# Sheet_4.net
KiCad netlist of a schematic drawn in Altium Designer
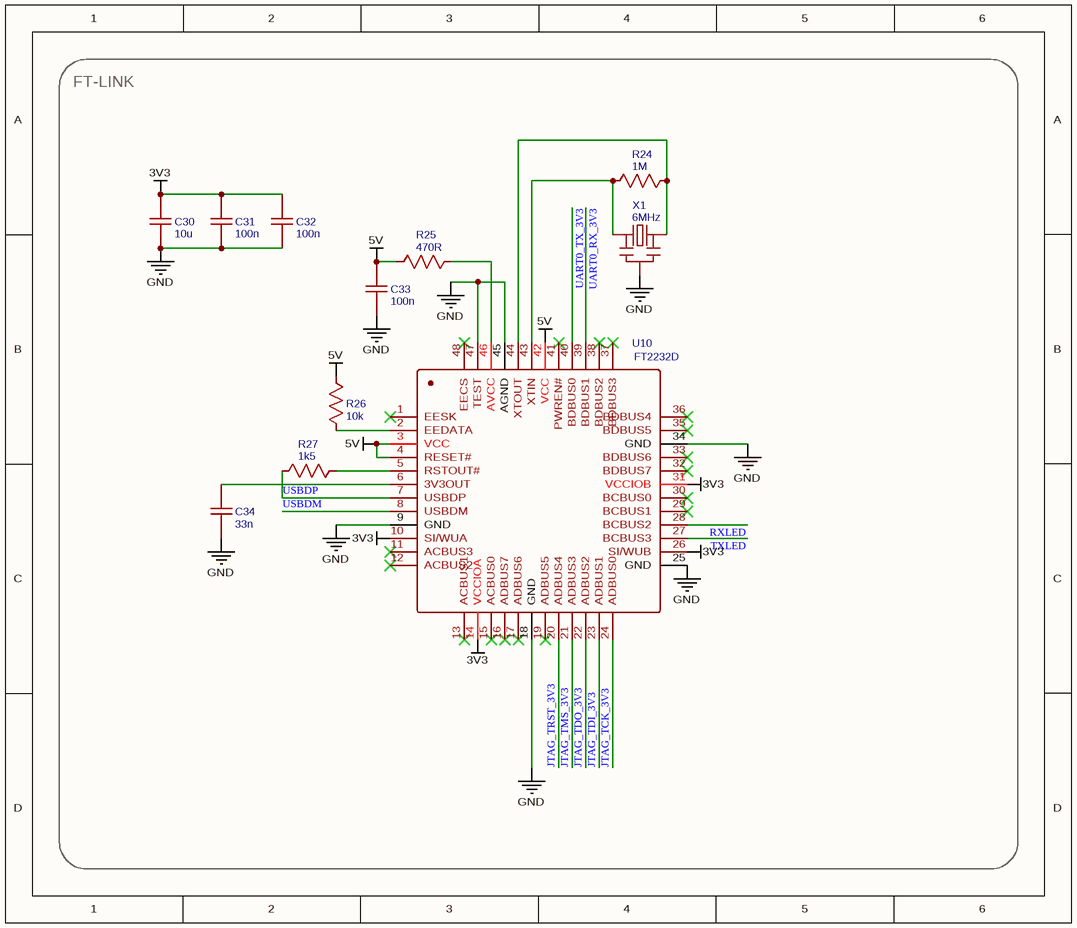
[diagram p0: Sheet_4.schdoc]

(export (version "E")
  (design (tool "Eeschema 10.0.6"))
  (components
    (comp (ref "C30")
      (value "10u")
      (footprint "CAPA-0603")
      (fields
        (field (name "BOM_SUPPLIER PART") "C19702")
        (field (name "BOM_MANUFACTURER PART") "CL10A106KP8NNNC")
      )
      (libsource (lib "altium-import") (part "root_1_10u_"))
    )
    (comp (ref "C31")
      (value "100n")
      (footprint "CAPA-0402")
      (fields
        (field (name "BOM_SUPPLIER PART") "C307331")
        (field (name "BOM_MANUFACTURER PART") "CL05B104KB54PNC")
      )
      (libsource (lib "altium-import") (part "root_1_100n_"))
    )
    (comp (ref "C32")
      (value "100n")
      (footprint "CAPA-0402")
      (fields
        (field (name "BOM_SUPPLIER PART") "C307331")
        (field (name "BOM_MANUFACTURER PART") "CL05B104KB54PNC")
      )
      (libsource (lib "altium-import") (part "root_1_100n_"))
    )
    (comp (ref "C33")
      (value "100n")
      (footprint "CAPA-0402")
      (fields
        (field (name "BOM_SUPPLIER PART") "C307331")
        (field (name "BOM_MANUFACTURER PART") "CL05B104KB54PNC")
      )
      (libsource (lib "altium-import") (part "root_1_100n_"))
    )
    (comp (ref "C34")
      (value "33n")
      (footprint "CAPA-0603")
      (fields
        (field (name "BOM_SUPPLIER PART") "C21117")
        (field (name "BOM_MANUFACTURER PART") "CL10B333KB8NNNC")
      )
      (libsource (lib "altium-import") (part "root_1_33n_"))
    )
    (comp (ref "R24")
      (value "1M")
      (footprint "RES-0402")
      (fields
        (field (name "BOM_SUPPLIER PART") "C26083")
        (field (name "BOM_MANUFACTURER PART") "0402WGF1004TCE")
      )
      (libsource (lib "altium-import") (part "root_0_1M_"))
    )
    (comp (ref "R25")
      (value "470R")
      (footprint "RES-0402")
      (fields
        (field (name "BOM_SUPPLIER PART") "C25117")
        (field (name "BOM_MANUFACTURER PART") "0402WGF4700TCE")
      )
      (libsource (lib "altium-import") (part "root_0_470R_"))
    )
    (comp (ref "R26")
      (value "10k")
      (footprint "RES-0402")
      (fields
        (field (name "BOM_SUPPLIER PART") "C25744")
        (field (name "BOM_MANUFACTURER PART") "0402WGF1002TCE")
      )
      (libsource (lib "altium-import") (part "root_3_10k_"))
    )
    (comp (ref "R27")
      (value "1k5")
      (footprint "RES-0402")
      (fields
        (field (name "BOM_SUPPLIER PART") "C25867")
        (field (name "BOM_MANUFACTURER PART") "0402WGF1501TCE")
      )
      (libsource (lib "altium-import") (part "root_0_1k5_"))
    )
    (comp (ref "U10")
      (value "FT2232D")
      (footprint "LQFP-48_L7.0-W7.0-P0.50-LS9.0-BL")
      (fields (field (name "BOM_SUPPLIER PART") "C428116"))
      (libsource (lib "altium-import") (part "root_0_FT2232D_"))
    )
    (comp (ref "X1")
      (value "6MHz")
      (footprint "CRYSTAL-SMD_3P-L4.5-W2.0-L")
      (fields
        (field (name "BOM_MANUFACTURER PART") "CSTCR6M00G53-R0")
        (field (name "BOM_SUPPLIER PART") "C85845")
      )
      (libsource (lib "altium-import") (part "root_0_6MHz_"))
    )
  )
  (nets
    (net (code "1") (name "/JTAG_TCK_3V3") (class "Default")
      (node (ref "U10") (pin "24") (pinfunction "ADBUS0_24") (pintype "passive"))
    )
    (net (code "2") (name "/JTAG_TDI_3V3") (class "Default")
      (node (ref "U10") (pin "23") (pinfunction "ADBUS1_23") (pintype "passive"))
    )
    (net (code "3") (name "/JTAG_TDO_3V3") (class "Default")
      (node (ref "U10") (pin "22") (pinfunction "ADBUS2_22") (pintype "passive"))
    )
    (net (code "4") (name "/JTAG_TMS_3V3") (class "Default")
      (node (ref "U10") (pin "21") (pinfunction "ADBUS3_21") (pintype "passive"))
    )
    (net (code "5") (name "/JTAG_TRST_3V3") (class "Default")
      (node (ref "U10") (pin "20") (pinfunction "ADBUS4_20") (pintype "passive"))
    )
    (net (code "6") (name "/RXLED") (class "Default")
      (node (ref "U10") (pin "28") (pinfunction "BCBUS2_28") (pintype "passive"))
    )
    (net (code "7") (name "/TXLED") (class "Default")
      (node (ref "U10") (pin "27") (pinfunction "BCBUS3_27") (pintype "passive"))
    )
    (net (code "8") (name "/UART0_RX_3V3") (class "Default")
      (node (ref "U10") (pin "39") (pinfunction "BDBUS1_39") (pintype "passive"))
    )
    (net (code "9") (name "/UART0_TX_3V3") (class "Default")
      (node (ref "U10") (pin "40") (pinfunction "BDBUS0_40") (pintype "passive"))
    )
    (net (code "10") (name "/USBDM") (class "Default")
      (node (ref "U10") (pin "8") (pinfunction "USBDM_8") (pintype "passive"))
    )
    (net (code "11") (name "/USBDP") (class "Default")
      (node (ref "R27") (pin "1") (pinfunction "1_1") (pintype "passive"))
      (node (ref "U10") (pin "7") (pinfunction "USBDP_7") (pintype "passive"))
    )
    (net (code "12") (name "3V3") (class "Default")
      (node (ref "C30") (pin "2") (pinfunction "2_2") (pintype "passive"))
      (node (ref "C31") (pin "2") (pinfunction "2_2") (pintype "passive"))
      (node (ref "C32") (pin "2") (pinfunction "2_2") (pintype "passive"))
      (node (ref "U10") (pin "10") (pinfunction "SI/WUA_10") (pintype "passive"))
      (node (ref "U10") (pin "14") (pinfunction "VCCIOA_14") (pintype "passive"))
      (node (ref "U10") (pin "26") (pinfunction "SI/WUB_26") (pintype "passive"))
      (node (ref "U10") (pin "31") (pinfunction "VCCIOB_31") (pintype "passive"))
    )
    (net (code "13") (name "5V") (class "Default")
      (node (ref "C33") (pin "2") (pinfunction "2_2") (pintype "passive"))
      (node (ref "R25") (pin "1") (pinfunction "1_1") (pintype "passive"))
      (node (ref "R26") (pin "1") (pinfunction "1_1") (pintype "passive"))
      (node (ref "U10") (pin "3") (pinfunction "VCC_3") (pintype "passive"))
      (node (ref "U10") (pin "4") (pinfunction "RESET#_4") (pintype "passive"))
      (node (ref "U10") (pin "42") (pinfunction "VCC_42") (pintype "passive"))
    )
    (net (code "14") (name "GND") (class "Default")
      (node (ref "C30") (pin "1") (pinfunction "1_1") (pintype "passive"))
      (node (ref "C31") (pin "1") (pinfunction "1_1") (pintype "passive"))
      (node (ref "C32") (pin "1") (pinfunction "1_1") (pintype "passive"))
      (node (ref "C33") (pin "1") (pinfunction "1_1") (pintype "passive"))
      (node (ref "C34") (pin "1") (pinfunction "1_1") (pintype "passive"))
      (node (ref "U10") (pin "18") (pinfunction "GND_18") (pintype "passive"))
      (node (ref "U10") (pin "25") (pinfunction "GND_25") (pintype "passive"))
      (node (ref "U10") (pin "34") (pinfunction "GND_34") (pintype "passive"))
      (node (ref "U10") (pin "45") (pinfunction "AGND_45") (pintype "passive"))
      (node (ref "U10") (pin "47") (pinfunction "TEST_47") (pintype "passive"))
      (node (ref "U10") (pin "9") (pinfunction "GND_9") (pintype "passive"))
      (node (ref "X1") (pin "2") (pinfunction "GND_2") (pintype "passive"))
    )
    (net (code "15") (name "Net-(U10-3V3OUT)") (class "Default")
      (node (ref "C34") (pin "2") (pinfunction "2_2") (pintype "passive"))
      (node (ref "U10") (pin "6") (pinfunction "3V3OUT_6") (pintype "passive"))
    )
    (net (code "16") (name "Net-(U10-AVCC)") (class "Default")
      (node (ref "R25") (pin "2") (pinfunction "2_2") (pintype "passive"))
      (node (ref "U10") (pin "46") (pinfunction "AVCC_46") (pintype "passive"))
    )
    (net (code "17") (name "Net-(U10-EEDATA)") (class "Default")
      (node (ref "R26") (pin "2") (pinfunction "2_2") (pintype "passive"))
      (node (ref "U10") (pin "2") (pinfunction "EEDATA_2") (pintype "passive"))
    )
    (net (code "18") (name "Net-(U10-RSTOUT#)") (class "Default")
      (node (ref "R27") (pin "2") (pinfunction "2_2") (pintype "passive"))
      (node (ref "U10") (pin "5") (pinfunction "RSTOUT#_5") (pintype "passive"))
    )
    (net (code "19") (name "Net-(U10-XTIN)") (class "Default")
      (node (ref "R24") (pin "1") (pinfunction "1_1") (pintype "passive"))
      (node (ref "U10") (pin "43") (pinfunction "XTIN_43") (pintype "passive"))
      (node (ref "X1") (pin "1") (pinfunction "IN_1") (pintype "passive"))
    )
    (net (code "20") (name "Net-(U10-XTOUT)") (class "Default")
      (node (ref "R24") (pin "2") (pinfunction "2_2") (pintype "passive"))
      (node (ref "U10") (pin "44") (pinfunction "XTOUT_44") (pintype "passive"))
      (node (ref "X1") (pin "3") (pinfunction "OUT_3") (pintype "passive"))
    )
    (net (code "21") (name "unconnected-(U10-ACBUS0-Pad15)") (class "Default")
      (node (ref "U10") (pin "15") (pinfunction "ACBUS0_15") (pintype "passive+no_connect"))
    )
    (net (code "22") (name "unconnected-(U10-ACBUS1-Pad13)") (class "Default")
      (node (ref "U10") (pin "13") (pinfunction "ACBUS1_13") (pintype "passive+no_connect"))
    )
    (net (code "23") (name "unconnected-(U10-ACBUS2-Pad12)") (class "Default")
      (node (ref "U10") (pin "12") (pinfunction "ACBUS2_12") (pintype "passive+no_connect"))
    )
    (net (code "24") (name "unconnected-(U10-ACBUS3-Pad11)") (class "Default")
      (node (ref "U10") (pin "11") (pinfunction "ACBUS3_11") (pintype "passive+no_connect"))
    )
    (net (code "25") (name "unconnected-(U10-ADBUS5-Pad19)") (class "Default")
      (node (ref "U10") (pin "19") (pinfunction "ADBUS5_19") (pintype "passive+no_connect"))
    )
    (net (code "26") (name "unconnected-(U10-ADBUS6-Pad17)") (class "Default")
      (node (ref "U10") (pin "17") (pinfunction "ADBUS6_17") (pintype "passive+no_connect"))
    )
    (net (code "27") (name "unconnected-(U10-ADBUS7-Pad16)") (class "Default")
      (node (ref "U10") (pin "16") (pinfunction "ADBUS7_16") (pintype "passive+no_connect"))
    )
    (net (code "28") (name "unconnected-(U10-BCBUS0-Pad30)") (class "Default")
      (node (ref "U10") (pin "30") (pinfunction "BCBUS0_30") (pintype "passive+no_connect"))
    )
    (net (code "29") (name "unconnected-(U10-BCBUS1-Pad29)") (class "Default")
      (node (ref "U10") (pin "29") (pinfunction "BCBUS1_29") (pintype "passive+no_connect"))
    )
    (net (code "30") (name "unconnected-(U10-BDBUS2-Pad38)") (class "Default")
      (node (ref "U10") (pin "38") (pinfunction "BDBUS2_38") (pintype "passive+no_connect"))
    )
    (net (code "31") (name "unconnected-(U10-BDBUS3-Pad37)") (class "Default")
      (node (ref "U10") (pin "37") (pinfunction "BDBUS3_37") (pintype "passive+no_connect"))
    )
    (net (code "32") (name "unconnected-(U10-BDBUS4-Pad36)") (class "Default")
      (node (ref "U10") (pin "36") (pinfunction "BDBUS4_36") (pintype "passive+no_connect"))
    )
    (net (code "33") (name "unconnected-(U10-BDBUS5-Pad35)") (class "Default")
      (node (ref "U10") (pin "35") (pinfunction "BDBUS5_35") (pintype "passive+no_connect"))
    )
    (net (code "34") (name "unconnected-(U10-BDBUS6-Pad33)") (class "Default")
      (node (ref "U10") (pin "33") (pinfunction "BDBUS6_33") (pintype "passive+no_connect"))
    )
    (net (code "35") (name "unconnected-(U10-BDBUS7-Pad32)") (class "Default")
      (node (ref "U10") (pin "32") (pinfunction "BDBUS7_32") (pintype "passive+no_connect"))
    )
    (net (code "36") (name "unconnected-(U10-EECS-Pad48)") (class "Default")
      (node (ref "U10") (pin "48") (pinfunction "EECS_48") (pintype "passive+no_connect"))
    )
    (net (code "37") (name "unconnected-(U10-EESK-Pad1)") (class "Default")
      (node (ref "U10") (pin "1") (pinfunction "EESK_1") (pintype "passive+no_connect"))
    )
    (net (code "38") (name "unconnected-(U10-PWREN#-Pad41)") (class "Default")
      (node (ref "U10") (pin "41") (pinfunction "PWREN#_41") (pintype "passive+no_connect"))
    )
  )
)
